# klokun-var.net
KiCad netlist of a schematic drawn in Altium Designer
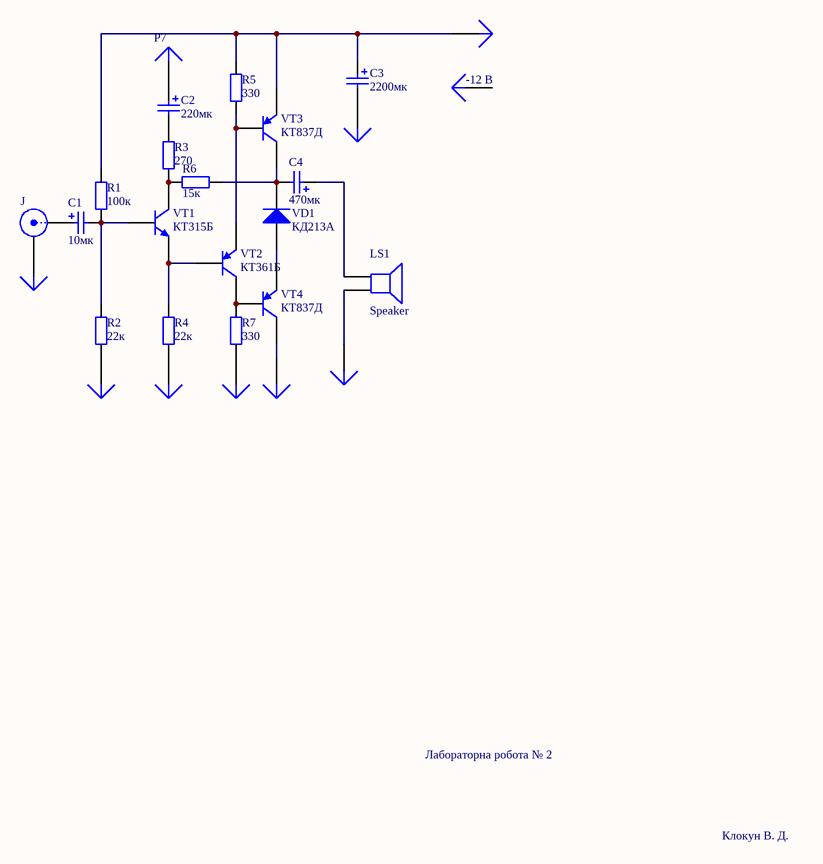
[diagram p0: klokun-var.SchDoc]

(export (version "E")
  (design (tool "Eeschema 10.0.6"))
  (components
    (comp (ref "C1")
      (value "10мк")
      (footprint "CAPPA14.05-10.5x6.3")
      (description "Polarized Capacitor (Axial)")
      (fields (field (name "Comment") "Cap Pol2") (field (name "PUBLISHER") "Altium Limited"))
      (libsource (lib "Miscellaneous Devices") (part "Cap Pol2"))
    )
    (comp (ref "C2")
      (value "220мк")
      (footprint "CAPPA14.05-10.5x6.3")
      (description "Polarized Capacitor (Axial)")
      (fields (field (name "Comment") "Cap Pol2") (field (name "PUBLISHER") "Altium Limited"))
      (libsource (lib "Miscellaneous Devices") (part "Cap Pol2"))
    )
    (comp (ref "C3")
      (value "2200мк")
      (footprint "CAPPA14.05-10.5x6.3")
      (description "Polarized Capacitor (Axial)")
      (fields (field (name "Comment") "Cap Pol2") (field (name "PUBLISHER") "Altium Limited"))
      (libsource (lib "Miscellaneous Devices") (part "Cap Pol2"))
    )
    (comp (ref "C4")
      (value "470мк")
      (footprint "CAPPA14.05-10.5x6.3")
      (description "Polarized Capacitor (Axial)")
      (fields (field (name "Comment") "Cap Pol2") (field (name "PUBLISHER") "Altium Limited"))
      (libsource (lib "Miscellaneous Devices") (part "Cap Pol2"))
    )
    (comp (ref "J")
      (value "BNC")
      (footprint "BNC_RA CON")
      (description "BNC Elbow Connector")
      (fields (field (name "PUBLISHER") "Altium Limited"))
      (libsource (lib "Miscellaneous Connectors") (part "BNC"))
    )
    (comp (ref "LS1")
      (value "Speaker")
      (footprint "PIN2")
      (description "Loudspeaker")
      (fields (field (name "PUBLISHER") "Altium Limited"))
      (libsource (lib "Miscellaneous Devices") (part "Speaker"))
    )
    (comp (ref "P1")
      (value "Plug")
      (footprint "PIN1")
      (fields (field (name "PUBLISHER") "Altium Limited"))
      (libsource (lib "Miscellaneous Connectors") (part "Plug"))
    )
    (comp (ref "P2")
      (value "Plug")
      (footprint "PIN1")
      (fields (field (name "PUBLISHER") "Altium Limited"))
      (libsource (lib "Miscellaneous Connectors") (part "Plug"))
    )
    (comp (ref "P3")
      (value "Plug")
      (footprint "PIN1")
      (fields (field (name "PUBLISHER") "Altium Limited"))
      (libsource (lib "Miscellaneous Connectors") (part "Plug"))
    )
    (comp (ref "P4")
      (value "Plug")
      (footprint "PIN1")
      (fields (field (name "PUBLISHER") "Altium Limited"))
      (libsource (lib "Miscellaneous Connectors") (part "Plug"))
    )
    (comp (ref "P5")
      (value "Plug")
      (footprint "PIN1")
      (fields (field (name "PUBLISHER") "Altium Limited"))
      (libsource (lib "Miscellaneous Connectors") (part "Plug"))
    )
    (comp (ref "P6")
      (value "Plug")
      (footprint "PIN1")
      (fields (field (name "PUBLISHER") "Altium Limited"))
      (libsource (lib "Miscellaneous Connectors") (part "Plug"))
    )
    (comp (ref "P7")
      (value "Plug")
      (footprint "PIN1")
      (fields (field (name "PUBLISHER") "Altium Limited"))
      (libsource (lib "Miscellaneous Connectors") (part "Plug"))
    )
    (comp (ref "P8")
      (value "Plug")
      (footprint "PIN1")
      (fields (field (name "PUBLISHER") "Altium Limited"))
      (libsource (lib "Miscellaneous Connectors") (part "Plug"))
    )
    (comp (ref "P9")
      (value "Plug")
      (footprint "PIN1")
      (fields (field (name "PUBLISHER") "Altium Limited"))
      (libsource (lib "Miscellaneous Connectors") (part "Plug"))
    )
    (comp (ref "P10")
      (value "-12 В")
      (footprint "PIN1")
      (description "Plug")
      (fields (field (name "PUBLISHER") "Altium Limited"))
      (libsource (lib "Miscellaneous Connectors") (part "Plug"))
    )
    (comp (ref "R1")
      (value "100к")
      (footprint "AXIAL-0.4")
      (description "Resistor")
      (fields (field (name "Comment") "Res2") (field (name "PUBLISHER") "Altium Limited"))
      (libsource (lib "Miscellaneous Devices") (part "Res2"))
    )
    (comp (ref "R2")
      (value "22к")
      (footprint "AXIAL-0.4")
      (description "Resistor")
      (fields (field (name "Comment") "Res2") (field (name "PUBLISHER") "Altium Limited"))
      (libsource (lib "Miscellaneous Devices") (part "Res2"))
    )
    (comp (ref "R3")
      (value "270")
      (footprint "AXIAL-0.4")
      (description "Resistor")
      (fields (field (name "Comment") "Res2") (field (name "PUBLISHER") "Altium Limited"))
      (libsource (lib "Miscellaneous Devices") (part "Res2"))
    )
    (comp (ref "R4")
      (value "22к")
      (footprint "AXIAL-0.4")
      (description "Resistor")
      (fields (field (name "Comment") "Res2") (field (name "PUBLISHER") "Altium Limited"))
      (libsource (lib "Miscellaneous Devices") (part "Res2"))
    )
    (comp (ref "R5")
      (value "330")
      (footprint "AXIAL-0.4")
      (description "Resistor")
      (fields (field (name "Comment") "Res2") (field (name "PUBLISHER") "Altium Limited"))
      (libsource (lib "Miscellaneous Devices") (part "Res2"))
    )
    (comp (ref "R6")
      (value "15к")
      (footprint "AXIAL-0.4")
      (description "Resistor")
      (fields (field (name "Comment") "Res2") (field (name "PUBLISHER") "Altium Limited"))
      (libsource (lib "") (part "Res2_1"))
    )
    (comp (ref "R7")
      (value "330")
      (footprint "AXIAL-0.4")
      (description "Resistor")
      (fields (field (name "Comment") "Res2") (field (name "PUBLISHER") "Altium Limited"))
      (libsource (lib "Miscellaneous Devices") (part "Res2"))
    )
    (comp (ref "VD1")
      (value "КД213А")
      (footprint "SMC")
      (description "Default Diode")
      (fields (field (name "PUBLISHER") "Altium Limited"))
      (libsource (lib "Miscellaneous Devices") (part "Diode"))
    )
    (comp (ref "VT1")
      (value "КТ315Б")
      (footprint "TO-226")
      (description "NPN Bipolar Transistor")
      (fields (field (name "PUBLISHER") "Altium Limited"))
      (libsource (lib "Miscellaneous Devices") (part "NPN"))
    )
    (comp (ref "VT2")
      (value "КТ361Б")
      (footprint "SOT-23B")
      (description "PNP Bipolar Transistor")
      (fields (field (name "PUBLISHER") "Altium Limited"))
      (libsource (lib "Miscellaneous Devices") (part "PNP"))
    )
    (comp (ref "VT3")
      (value "КТ837Д")
      (footprint "SOT-23B")
      (description "PNP Bipolar Transistor")
      (fields (field (name "PUBLISHER") "Altium Limited"))
      (libsource (lib "Miscellaneous Devices") (part "PNP"))
    )
    (comp (ref "VT4")
      (value "КТ837Д")
      (footprint "SOT-23B")
      (description "PNP Bipolar Transistor")
      (fields (field (name "PUBLISHER") "Altium Limited"))
      (libsource (lib "Miscellaneous Devices") (part "PNP"))
    )
  )
  (nets
    (net (code "1") (name "Net-(C2-Pad1)") (class "Default")
      (node (ref "C2") (pin "1") (pinfunction "1_1") (pintype "passive"))
      (node (ref "P7") (pin "1") (pinfunction "1_1") (pintype "passive"))
    )
    (net (code "2") (name "Net-(C2-Pad2)") (class "Default")
      (node (ref "C2") (pin "2") (pinfunction "2_2") (pintype "passive"))
      (node (ref "R3") (pin "2") (pinfunction "2_2") (pintype "passive"))
    )
    (net (code "3") (name "Net-(C3-Pad2)") (class "Default")
      (node (ref "C3") (pin "2") (pinfunction "2_2") (pintype "passive"))
      (node (ref "P1") (pin "1") (pinfunction "1_1") (pintype "passive"))
    )
    (net (code "4") (name "Net-(C4-Pad1)") (class "Default")
      (node (ref "C4") (pin "1") (pinfunction "1_1") (pintype "passive"))
      (node (ref "LS1") (pin "1") (pinfunction "1_1") (pintype "passive"))
    )
    (net (code "5") (name "Net-(J-X)") (class "Default")
      (node (ref "C1") (pin "1") (pinfunction "1_1") (pintype "passive"))
      (node (ref "J") (pin "1") (pinfunction "X_1") (pintype "passive"))
    )
    (net (code "6") (name "Net-(J-Y)") (class "Default")
      (node (ref "J") (pin "2") (pinfunction "Y_2") (pintype "passive"))
      (node (ref "P9") (pin "1") (pinfunction "1_1") (pintype "passive"))
    )
    (net (code "7") (name "Net-(LS1-Pad2)") (class "Default")
      (node (ref "LS1") (pin "2") (pinfunction "2_2") (pintype "passive"))
      (node (ref "P2") (pin "1") (pinfunction "1_1") (pintype "passive"))
    )
    (net (code "8") (name "Net-(P3-Pad1)") (class "Default")
      (node (ref "P3") (pin "1") (pinfunction "1_1") (pintype "passive"))
      (node (ref "R7") (pin "1") (pinfunction "1_1") (pintype "passive"))
    )
    (net (code "9") (name "Net-(P4-Pad1)") (class "Default")
      (node (ref "P4") (pin "1") (pinfunction "1_1") (pintype "passive"))
      (node (ref "R4") (pin "1") (pinfunction "1_1") (pintype "passive"))
    )
    (net (code "10") (name "Net-(P5-Pad1)") (class "Default")
      (node (ref "P5") (pin "1") (pinfunction "1_1") (pintype "passive"))
      (node (ref "R2") (pin "1") (pinfunction "1_1") (pintype "passive"))
    )
    (net (code "11") (name "Net-(VD1-A)") (class "Default")
      (node (ref "VD1") (pin "1") (pinfunction "A_1") (pintype "passive"))
      (node (ref "VT4") (pin "3") (pinfunction "E_3") (pintype "passive"))
    )
    (net (code "12") (name "Net-(VD1-K)") (class "Default")
      (node (ref "C4") (pin "2") (pinfunction "2_2") (pintype "passive"))
      (node (ref "R6") (pin "2") (pinfunction "2_2") (pintype "passive"))
      (node (ref "VD1") (pin "2") (pinfunction "K_2") (pintype "passive"))
      (node (ref "VT3") (pin "1") (pinfunction "C_1") (pintype "passive"))
    )
    (net (code "13") (name "Net-(VT1-B)") (class "Default")
      (node (ref "C1") (pin "2") (pinfunction "2_2") (pintype "passive"))
      (node (ref "R1") (pin "1") (pinfunction "1_1") (pintype "passive"))
      (node (ref "R2") (pin "2") (pinfunction "2_2") (pintype "passive"))
      (node (ref "VT1") (pin "2") (pinfunction "B_2") (pintype "passive"))
    )
    (net (code "14") (name "Net-(VT1-C)") (class "Default")
      (node (ref "R3") (pin "1") (pinfunction "1_1") (pintype "passive"))
      (node (ref "R6") (pin "1") (pinfunction "1_1") (pintype "passive"))
      (node (ref "VT1") (pin "1") (pinfunction "C_1") (pintype "passive"))
    )
    (net (code "15") (name "Net-(VT1-E)") (class "Default")
      (node (ref "R4") (pin "2") (pinfunction "2_2") (pintype "passive"))
      (node (ref "VT1") (pin "3") (pinfunction "E_3") (pintype "passive"))
      (node (ref "VT2") (pin "2") (pinfunction "B_2") (pintype "passive"))
    )
    (net (code "16") (name "Net-(VT2-C)") (class "Default")
      (node (ref "R7") (pin "2") (pinfunction "2_2") (pintype "passive"))
      (node (ref "VT2") (pin "1") (pinfunction "C_1") (pintype "passive"))
      (node (ref "VT4") (pin "2") (pinfunction "B_2") (pintype "passive"))
    )
    (net (code "17") (name "Net-(VT2-E)") (class "Default")
      (node (ref "R5") (pin "1") (pinfunction "1_1") (pintype "passive"))
      (node (ref "VT2") (pin "3") (pinfunction "E_3") (pintype "passive"))
      (node (ref "VT3") (pin "2") (pinfunction "B_2") (pintype "passive"))
    )
    (net (code "18") (name "Net-(VT3-E)") (class "Default")
      (node (ref "C3") (pin "1") (pinfunction "1_1") (pintype "passive"))
      (node (ref "P6") (pin "1") (pinfunction "1_1") (pintype "passive"))
      (node (ref "R1") (pin "2") (pinfunction "2_2") (pintype "passive"))
      (node (ref "R5") (pin "2") (pinfunction "2_2") (pintype "passive"))
      (node (ref "VT3") (pin "3") (pinfunction "E_3") (pintype "passive"))
    )
    (net (code "19") (name "Net-(VT4-C)") (class "Default")
      (node (ref "P8") (pin "1") (pinfunction "1_1") (pintype "passive"))
      (node (ref "VT4") (pin "1") (pinfunction "C_1") (pintype "passive"))
    )
    (net (code "20") (name "unconnected-(P10-Pad1)") (class "Default")
      (node (ref "P10") (pin "1") (pinfunction "1_1") (pintype "passive"))
    )
  )
)
